# BeamMini.net
KiCad netlist of a schematic drawn in EAGLE
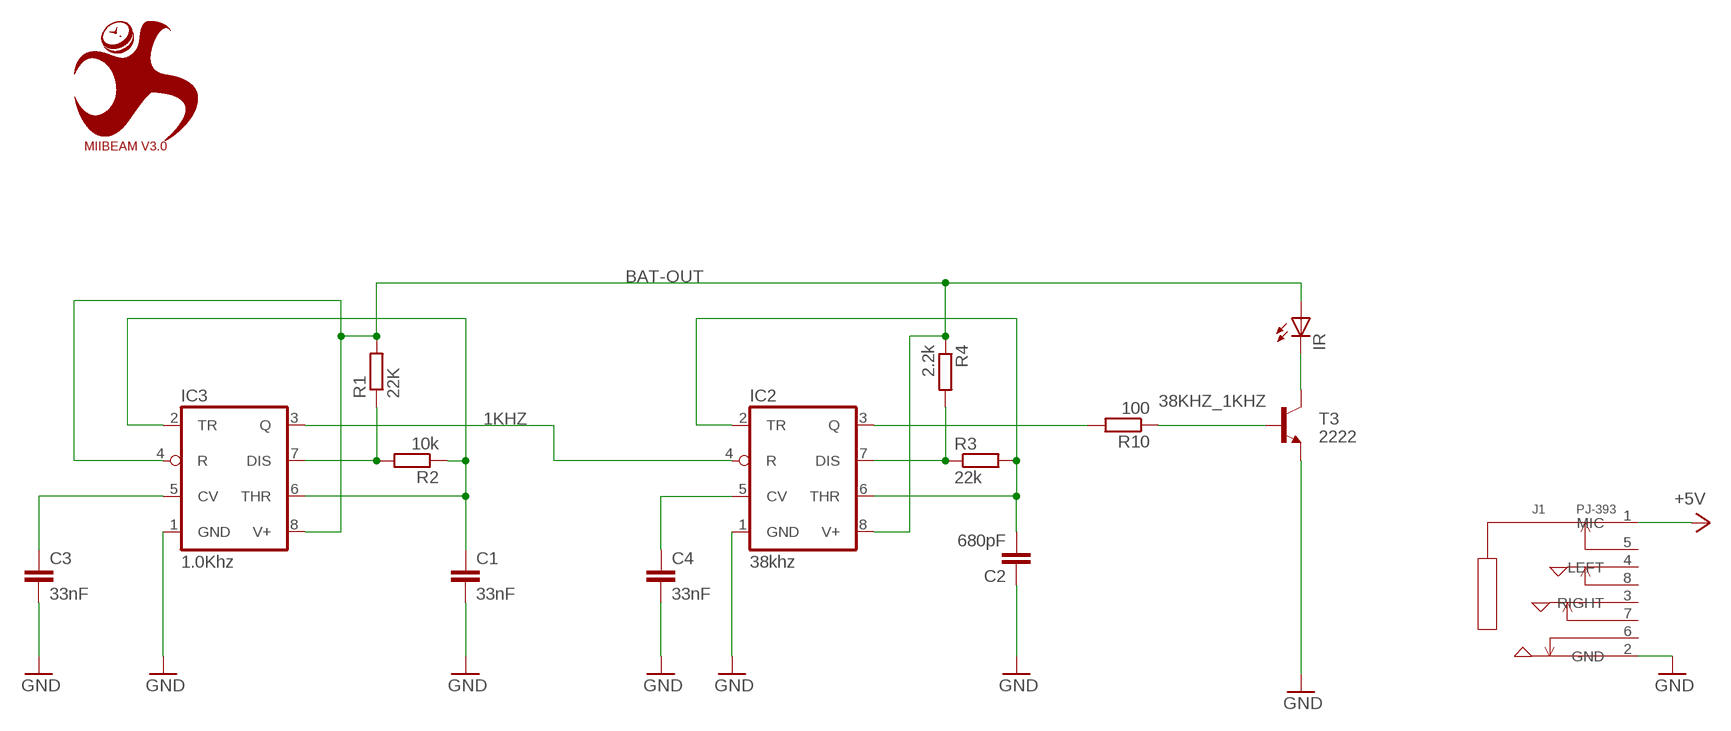
[diagram p0: schematic, sheet 1]
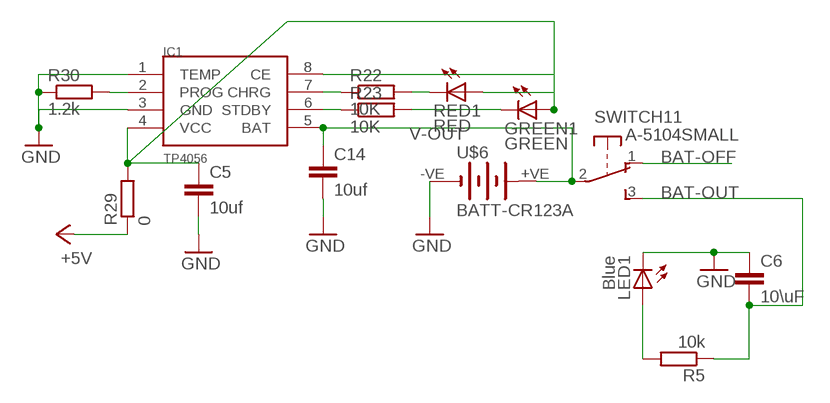
[diagram p1: schematic, sheet 2]

(export (version "E")
  (design (tool "Eeschema 10.0.6"))
  (components
    (comp (ref "C5")
      (value "10uf")
      (footprint "eagle-import:C0805")
      (libsource (lib "eagle-import") (part "C-EUC0805"))
    )
    (comp (ref "C6")
      (value "10\\uF")
      (footprint "eagle-import:C0805")
      (libsource (lib "eagle-import") (part "C-EUC0805"))
    )
    (comp (ref "C14")
      (value "10uf")
      (footprint "eagle-import:C0805")
      (libsource (lib "eagle-import") (part "C-EUC0805"))
    )
    (comp (ref "GREEN1")
      (value "GREEN")
      (footprint "eagle-import:CHIP-LED0805")
      (libsource (lib "eagle-import") (part "LEDCHIP-LED0805"))
    )
    (comp (ref "IC1")
      (value "TP4056")
      (footprint "eagle-import:SOP-8")
      (libsource (lib "eagle-import") (part "TP4056"))
    )
    (comp (ref "LED1")
      (value "Blue")
      (footprint "eagle-import:CHIP-LED0805")
      (libsource (lib "eagle-import") (part "LEDCHIP-LED0805"))
    )
    (comp (ref "R5")
      (value "10k")
      (footprint "eagle-import:M0805")
      (libsource (lib "eagle-import") (part "R-EU_M0805"))
    )
    (comp (ref "R22")
      (value "10K")
      (footprint "eagle-import:R0805")
      (libsource (lib "eagle-import") (part "R-EU_R0805"))
    )
    (comp (ref "R23")
      (value "10K")
      (footprint "eagle-import:R0805")
      (libsource (lib "eagle-import") (part "R-EU_R0805"))
    )
    (comp (ref "R29")
      (value "0")
      (footprint "eagle-import:R0805")
      (libsource (lib "eagle-import") (part "R-EU_R0805"))
    )
    (comp (ref "R30")
      (value "1.2k")
      (footprint "eagle-import:R0805")
      (libsource (lib "eagle-import") (part "R-EU_R0805"))
    )
    (comp (ref "RED1")
      (value "RED")
      (footprint "eagle-import:CHIP-LED0805")
      (libsource (lib "eagle-import") (part "LEDCHIP-LED0805"))
    )
    (comp (ref "SWITCH1")
      (value "A-5104SMALL")
      (footprint "eagle-import:A-5104-SMALL")
      (libsource (lib "eagle-import") (part "A-5104SMALL"))
    )
    (comp (ref "U$6")
      (value "BATT-CR123A")
      (footprint "eagle-import:KEYSTONE-2_3A")
      (libsource (lib "eagle-import") (part "BATT-CR123A"))
    )
    (comp (ref "C1")
      (value "33nF")
      (footprint "eagle-import:C0805")
      (libsource (lib "eagle-import") (part "C-EUC0805"))
    )
    (comp (ref "C2")
      (value "680pF")
      (footprint "eagle-import:C0805")
      (libsource (lib "eagle-import") (part "C-EUC0805"))
    )
    (comp (ref "C3")
      (value "33nF")
      (footprint "eagle-import:C0805")
      (libsource (lib "eagle-import") (part "C-EUC0805"))
    )
    (comp (ref "C4")
      (value "33nF")
      (footprint "eagle-import:C0805")
      (libsource (lib "eagle-import") (part "C-EUC0805"))
    )
    (comp (ref "IC2")
      (value "38khz")
      (footprint "eagle-import:SO08")
      (libsource (lib "eagle-import") (part "555DNE"))
    )
    (comp (ref "IC3")
      (value "1.0Khz")
      (footprint "eagle-import:SO08")
      (libsource (lib "eagle-import") (part "555DNE"))
    )
    (comp (ref "IR")
      (value "LED5MM")
      (footprint "eagle-import:LED5MM")
      (libsource (lib "eagle-import") (part "LED5MM"))
    )
    (comp (ref "J1")
      (value "PJ-393")
      (footprint "eagle-import:AUDIO8P-SMD-3.5-14.5X6.1X4.0MM")
      (libsource (lib "eagle-import") (part "AUDIO-JACK-PJ-393(8P-SMD)"))
    )
    (comp (ref "R1")
      (value "22K")
      (footprint "eagle-import:M0805")
      (libsource (lib "eagle-import") (part "R-EU_M0805"))
    )
    (comp (ref "R2")
      (value "10k")
      (footprint "eagle-import:M0805")
      (libsource (lib "eagle-import") (part "R-EU_M0805"))
    )
    (comp (ref "R3")
      (value "22k")
      (footprint "eagle-import:M0805")
      (libsource (lib "eagle-import") (part "R-EU_M0805"))
    )
    (comp (ref "R4")
      (value "2.2k")
      (footprint "eagle-import:M0805")
      (libsource (lib "eagle-import") (part "R-EU_M0805"))
    )
    (comp (ref "R10")
      (value "100")
      (footprint "eagle-import:M0805")
      (libsource (lib "eagle-import") (part "R-EU_M0805"))
    )
    (comp (ref "T3")
      (value "2222")
      (footprint "eagle-import:SOT23")
      (libsource (lib "eagle-import") (part "TRANSISTOR_NPNSOT23"))
    )
    (comp (ref "U$1")
      (value "MIIBEAM V3.0")
      (footprint "eagle-import:MIICHRONO")
      (libsource (lib "eagle-import") (part "MIICHRONO"))
    )
  )
  (nets
    (net (code "1") (name "+5V") (class "Default")
      (node (ref "J1") (pin "1") (pinfunction "MIC_1") (pintype "bidirectional"))
      (node (ref "R29") (pin "1") (pinfunction "1_1") (pintype "passive"))
    )
    (net (code "2") (name "1KHZ") (class "Default")
      (node (ref "IC2") (pin "4") (pinfunction "R_4") (pintype "input"))
      (node (ref "IC3") (pin "3") (pinfunction "Q_3") (pintype "output"))
    )
    (net (code "3") (name "38KHZ_1KHZ") (class "Default")
      (node (ref "R10") (pin "1") (pinfunction "1_1") (pintype "passive"))
      (node (ref "T3") (pin "1") (pinfunction "B_1") (pintype "passive"))
    )
    (net (code "4") (name "BAT-OFF") (class "Default")
      (node (ref "SWITCH1") (pin "1") (pinfunction "O_1") (pintype "passive"))
    )
    (net (code "5") (name "BAT-OUT") (class "Default")
      (node (ref "C6") (pin "2") (pinfunction "2_2") (pintype "passive"))
      (node (ref "IC2") (pin "8") (pinfunction "V+_8") (pintype "power_in"))
      (node (ref "IC3") (pin "4") (pinfunction "R_4") (pintype "input"))
      (node (ref "IC3") (pin "8") (pinfunction "V+_8") (pintype "power_in"))
      (node (ref "IR") (pin "A") (pinfunction "A_A") (pintype "passive"))
      (node (ref "R1") (pin "2") (pinfunction "2_2") (pintype "passive"))
      (node (ref "R4") (pin "1") (pinfunction "1_1") (pintype "passive"))
      (node (ref "R5") (pin "1") (pinfunction "1_1") (pintype "passive"))
      (node (ref "SWITCH1") (pin "3") (pinfunction "S_3") (pintype "passive"))
    )
    (net (code "6") (name "GND") (class "Default")
      (node (ref "C1") (pin "2") (pinfunction "2_2") (pintype "passive"))
      (node (ref "C14") (pin "2") (pinfunction "2_2") (pintype "passive"))
      (node (ref "C2") (pin "1") (pinfunction "1_1") (pintype "passive"))
      (node (ref "C3") (pin "2") (pinfunction "2_2") (pintype "passive"))
      (node (ref "C4") (pin "2") (pinfunction "2_2") (pintype "passive"))
      (node (ref "C5") (pin "2") (pinfunction "2_2") (pintype "passive"))
      (node (ref "C6") (pin "1") (pinfunction "1_1") (pintype "passive"))
      (node (ref "IC1") (pin "1") (pinfunction "TEMP_1") (pintype "bidirectional"))
      (node (ref "IC1") (pin "3") (pinfunction "GND_3") (pintype "bidirectional"))
      (node (ref "IC2") (pin "1") (pinfunction "GND_1") (pintype "power_in"))
      (node (ref "IC3") (pin "1") (pinfunction "GND_1") (pintype "power_in"))
      (node (ref "J1") (pin "2") (pinfunction "GND_2") (pintype "bidirectional"))
      (node (ref "LED1") (pin "C") (pinfunction "C_C") (pintype "passive"))
      (node (ref "R30") (pin "1") (pinfunction "1_1") (pintype "passive"))
      (node (ref "T3") (pin "2") (pinfunction "E_2") (pintype "passive"))
      (node (ref "U$6") (pin "-VE") (pinfunction "-_-VE") (pintype "passive"))
    )
    (net (code "7") (name "Net-(GREEN1-PadC)") (class "Default")
      (node (ref "GREEN1") (pin "C") (pinfunction "C_C") (pintype "passive"))
      (node (ref "R23") (pin "2") (pinfunction "2_2") (pintype "passive"))
    )
    (net (code "8") (name "Net-(IC1-CE)") (class "Default")
      (node (ref "C5") (pin "1") (pinfunction "1_1") (pintype "passive"))
      (node (ref "GREEN1") (pin "A") (pinfunction "A_A") (pintype "passive"))
      (node (ref "IC1") (pin "4") (pinfunction "VCC_4") (pintype "bidirectional"))
      (node (ref "IC1") (pin "8") (pinfunction "CE_8") (pintype "bidirectional"))
      (node (ref "R29") (pin "2") (pinfunction "2_2") (pintype "passive"))
      (node (ref "RED1") (pin "A") (pinfunction "A_A") (pintype "passive"))
    )
    (net (code "9") (name "Net-(IC1-CHRG)") (class "Default")
      (node (ref "IC1") (pin "7") (pinfunction "CHRG_7") (pintype "bidirectional"))
      (node (ref "R22") (pin "1") (pinfunction "1_1") (pintype "passive"))
    )
    (net (code "10") (name "Net-(IC1-PROG)") (class "Default")
      (node (ref "IC1") (pin "2") (pinfunction "PROG_2") (pintype "bidirectional"))
      (node (ref "R30") (pin "2") (pinfunction "2_2") (pintype "passive"))
    )
    (net (code "11") (name "Net-(IC1-STDBY)") (class "Default")
      (node (ref "IC1") (pin "6") (pinfunction "STDBY_6") (pintype "bidirectional"))
      (node (ref "R23") (pin "1") (pinfunction "1_1") (pintype "passive"))
    )
    (net (code "12") (name "Net-(IC2-CV)") (class "Default")
      (node (ref "C4") (pin "1") (pinfunction "1_1") (pintype "passive"))
      (node (ref "IC2") (pin "5") (pinfunction "CV_5") (pintype "input"))
    )
    (net (code "13") (name "Net-(IC2-DIS)") (class "Default")
      (node (ref "IC2") (pin "7") (pinfunction "DIS_7") (pintype "input"))
      (node (ref "R3") (pin "1") (pinfunction "1_1") (pintype "passive"))
      (node (ref "R4") (pin "2") (pinfunction "2_2") (pintype "passive"))
    )
    (net (code "14") (name "Net-(IC2-Q)") (class "Default")
      (node (ref "IC2") (pin "3") (pinfunction "Q_3") (pintype "output"))
      (node (ref "R10") (pin "2") (pinfunction "2_2") (pintype "passive"))
    )
    (net (code "15") (name "Net-(IC2-THR)") (class "Default")
      (node (ref "C2") (pin "2") (pinfunction "2_2") (pintype "passive"))
      (node (ref "IC2") (pin "2") (pinfunction "TR_2") (pintype "input"))
      (node (ref "IC2") (pin "6") (pinfunction "THR_6") (pintype "input"))
      (node (ref "R3") (pin "2") (pinfunction "2_2") (pintype "passive"))
    )
    (net (code "16") (name "Net-(IC3-CV)") (class "Default")
      (node (ref "C3") (pin "1") (pinfunction "1_1") (pintype "passive"))
      (node (ref "IC3") (pin "5") (pinfunction "CV_5") (pintype "input"))
    )
    (net (code "17") (name "Net-(IC3-DIS)") (class "Default")
      (node (ref "IC3") (pin "7") (pinfunction "DIS_7") (pintype "input"))
      (node (ref "R1") (pin "1") (pinfunction "1_1") (pintype "passive"))
      (node (ref "R2") (pin "2") (pinfunction "2_2") (pintype "passive"))
    )
    (net (code "18") (name "Net-(IC3-THR)") (class "Default")
      (node (ref "C1") (pin "1") (pinfunction "1_1") (pintype "passive"))
      (node (ref "IC3") (pin "2") (pinfunction "TR_2") (pintype "input"))
      (node (ref "IC3") (pin "6") (pinfunction "THR_6") (pintype "input"))
      (node (ref "R2") (pin "1") (pinfunction "1_1") (pintype "passive"))
    )
    (net (code "19") (name "Net-(IR-C)") (class "Default")
      (node (ref "IR") (pin "K") (pinfunction "C_K") (pintype "passive"))
      (node (ref "T3") (pin "3") (pinfunction "C_3") (pintype "passive"))
    )
    (net (code "20") (name "Net-(LED1-PadA)") (class "Default")
      (node (ref "LED1") (pin "A") (pinfunction "A_A") (pintype "passive"))
      (node (ref "R5") (pin "2") (pinfunction "2_2") (pintype "passive"))
    )
    (net (code "21") (name "Net-(R22-Pad2)") (class "Default")
      (node (ref "R22") (pin "2") (pinfunction "2_2") (pintype "passive"))
      (node (ref "RED1") (pin "C") (pinfunction "C_C") (pintype "passive"))
    )
    (net (code "22") (name "V-OUT") (class "Default")
      (node (ref "C14") (pin "1") (pinfunction "1_1") (pintype "passive"))
      (node (ref "IC1") (pin "5") (pinfunction "BAT_5") (pintype "bidirectional"))
      (node (ref "SWITCH1") (pin "2") (pinfunction "P_2") (pintype "passive"))
      (node (ref "U$6") (pin "+VE") (pinfunction "+_+VE") (pintype "passive"))
    )
    (net (code "23") (name "unconnected-(J1-LEFT-Pad4)") (class "Default")
      (node (ref "J1") (pin "4") (pinfunction "LEFT_4") (pintype "bidirectional"))
    )
    (net (code "24") (name "unconnected-(J1-Pad5)") (class "Default")
      (node (ref "J1") (pin "5") (pinfunction "5_5") (pintype "bidirectional"))
    )
    (net (code "25") (name "unconnected-(J1-Pad6)") (class "Default")
      (node (ref "J1") (pin "6") (pinfunction "6_6") (pintype "bidirectional"))
    )
    (net (code "26") (name "unconnected-(J1-Pad7)") (class "Default")
      (node (ref "J1") (pin "7") (pinfunction "7_7") (pintype "bidirectional"))
    )
    (net (code "27") (name "unconnected-(J1-Pad8)") (class "Default")
      (node (ref "J1") (pin "8") (pinfunction "8_8") (pintype "bidirectional"))
    )
    (net (code "28") (name "unconnected-(J1-RIGHT-Pad3)") (class "Default")
      (node (ref "J1") (pin "3") (pinfunction "RIGHT_3") (pintype "bidirectional"))
    )
  )
)
